# Sheet1.net
KiCad netlist of a schematic drawn in Altium Designer
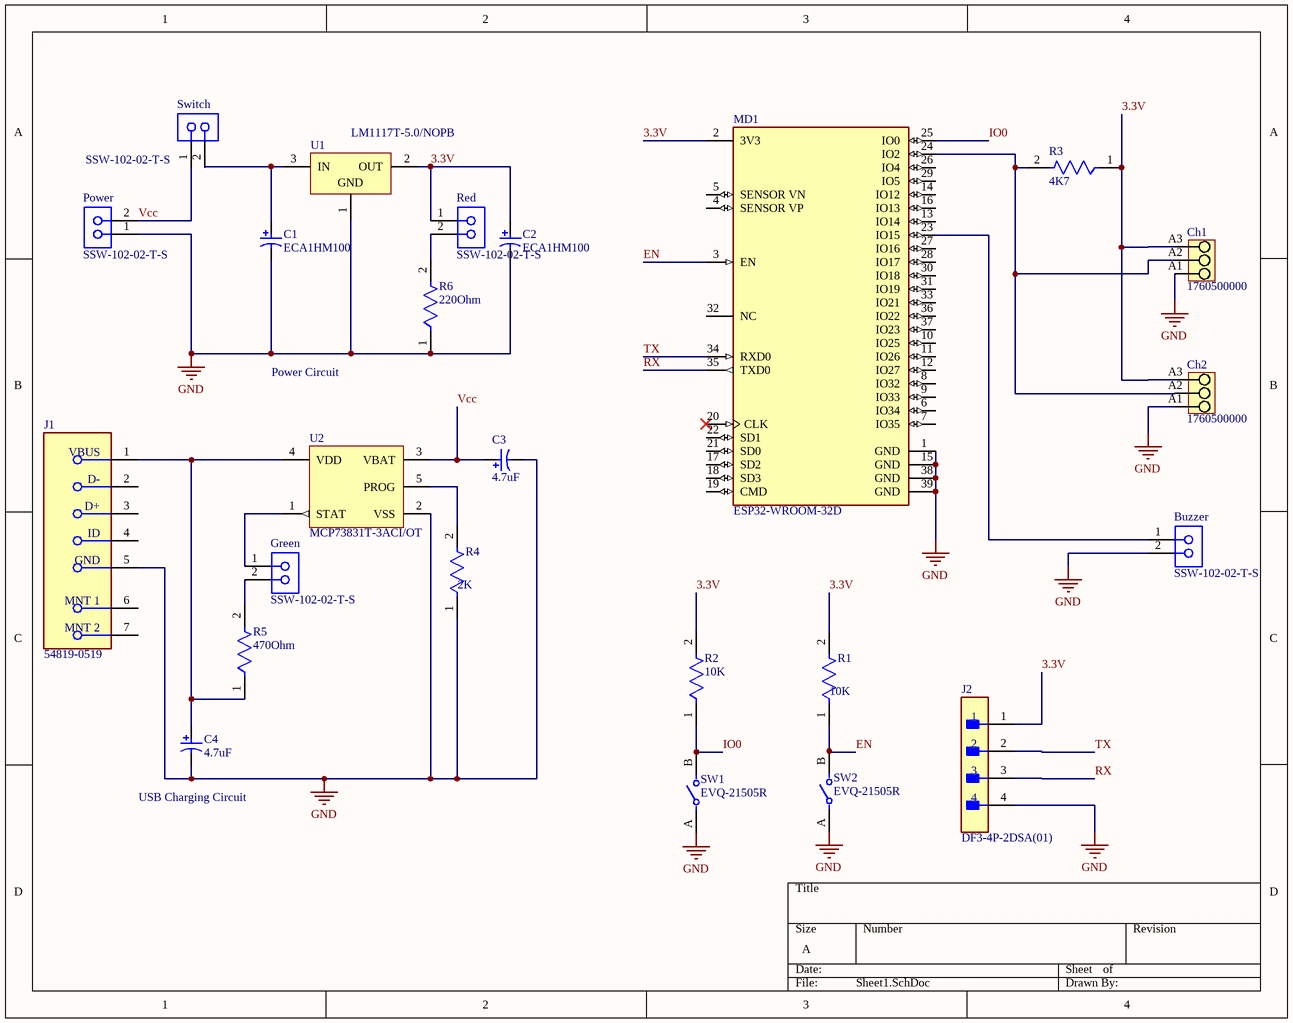
[diagram p0: Sheet1.SchDoc]

(export (version "E")
  (design (tool "Eeschema 10.0.6"))
  (components
    (comp (ref "Buzzer")
      (value "SSW-102-02-T-S")
      (footprint "SMTC-SSW-102-02-X-S")
      (description "SQ Post Socket, Through-hole, Vertical, -55 to 105 degC, 2.54 mm Pitch, 2-Pin, Female, RoHS")
      (fields (field (name "MANUFACTURER") "Samtec"))
      (libsource (lib "Altium Content Vault") (part "SMTC-SSW-102-02-X-S-X"))
    )
    (comp (ref "C1")
      (value "ECA1HM100")
      (footprint "CAPPR55-200-1100X500X1200")
      (description "Aluminum Electrolytic Capacitor, 10 uF, +/- 20%, 50 V, -40 to 85 degC, 2-Pin THD, RoHS, Bulk")
      (fields (field (name "MANUFACTURER") "Panasonic") (field (name "TOLERANCE") "20%"))
      (libsource (lib "Altium Content Vault") (part "CAP-P-2"))
    )
    (comp (ref "C2")
      (value "ECA1HM100")
      (footprint "CAPPR55-200-1100X500X1200")
      (description "Aluminum Electrolytic Capacitor, 10 uF, +/- 20%, 50 V, -40 to 85 degC, 2-Pin THD, RoHS, Bulk")
      (fields (field (name "MANUFACTURER") "Panasonic") (field (name "TOLERANCE") "20%"))
      (libsource (lib "Altium Content Vault") (part "CAP-P-2"))
    )
    (comp (ref "C3")
      (value "4.7uF")
      (footprint "CAPPR55-200-1100X500X1200")
      (description "Aluminum Electrolytic Capacitor, 4.7 uF, +/- 20%, 50 V, -40 to 85 degC, 2-Pin THD, RoHS, Bulk")
      (fields (field (name "VOLTAGE") "50V") (field (name "MANUFACTURER") "Panasonic"))
      (libsource (lib "Altium Content Vault") (part "CAP-P-2"))
    )
    (comp (ref "C4")
      (value "4.7uF")
      (footprint "CAPPR55-200-1100X500X1200")
      (description "Aluminum Electrolytic Capacitor, 4.7 uF, +/- 20%, 50 V, -40 to 85 degC, 2-Pin THD, RoHS, Bulk")
      (fields (field (name "VOLTAGE") "50V") (field (name "MANUFACTURER") "Panasonic"))
      (libsource (lib "Altium Content Vault") (part "CAP-P-2"))
    )
    (comp (ref "Ch1")
      (value "1760500000")
      (footprint "PM_5_08_90_03")
      (description "OMNIMATE Signal - series PM")
      (fields (field (name "MANUFACTURER") "Weidmueller"))
      (libsource (lib "Altium Content Vault") (part "Terminal_03_1x03"))
    )
    (comp (ref "Ch2")
      (value "1760500000")
      (footprint "PM_5_08_90_03")
      (description "OMNIMATE Signal - series PM")
      (fields (field (name "MANUFACTURER") "Weidmueller"))
      (libsource (lib "Altium Content Vault") (part "Terminal_03_1x03"))
    )
    (comp (ref "Green")
      (value "SSW-102-02-T-S")
      (footprint "SMTC-SSW-102-02-X-S")
      (description "SQ Post Socket, Through-hole, Vertical, -55 to 105 degC, 2.54 mm Pitch, 2-Pin, Female, RoHS")
      (fields (field (name "MANUFACTURER") "Samtec"))
      (libsource (lib "Altium Content Vault") (part "SMTC-SSW-102-02-X-S-X"))
    )
    (comp (ref "J1")
      (value "54819-0519")
      (footprint "FP-54819-0519-MFG")
      (description "CONN RCPT USB2.0 MINI B 5P R/A")
      (libsource (lib "Altium Content Vault") (part "0bee2869d159fa7a73e2a5ef735a9a6"))
    )
    (comp (ref "J2")
      (value "DF3-4P-2DSA(01)")
      (footprint "FP-DF3-4P-2DSA_01-MFG")
      (description "CONN HEADER VERT 4POS 2MM")
      (libsource (lib "Altium Content Vault") (part "299a8cea1bdcbc3624fe62c390fa72c"))
    )
    (comp (ref "MD1")
      (value "ESP32-WROOM-32D")
      (footprint "FP-ESP32-WROOM-32D-MFG")
      (description "WIFI MODULE 32MBITS SPI FLASH")
      (fields
        (field (name "OCTOPART") "https://octopart.com/esp32-wroom-32d-espressif+systems-91040050")
        (field (name "MANUFACTURER") "Espressif Systems")
      )
      (libsource (lib "Altium Content Vault") (part "a031a76f8c27026a7a7f4657ff233a3"))
    )
    (comp (ref "Power")
      (value "SSW-102-02-T-S")
      (footprint "SMTC-SSW-102-02-X-S")
      (description "SQ Post Socket, Through-hole, Vertical, -55 to 105 degC, 2.54 mm Pitch, 2-Pin, Female, RoHS")
      (fields (field (name "MANUFACTURER") "Samtec"))
      (libsource (lib "Altium Content Vault") (part "SMTC-SSW-102-02-X-S-X"))
    )
    (comp (ref "R1")
      (value "10K")
      (footprint "FP-CF18-MFG")
      (description "RES 10K OHM 1/8W 5% CF AXIAL")
      (fields
        (field (name "MANUFACTURER PART NUMBER") "CF18JT10K0")
        (field (name "MANUFACTURER") "Stackpole Electronics")
      )
      (libsource (lib "Altium Content Vault") (part "1029c3af85768c4190bb7ad29bc67b5"))
    )
    (comp (ref "R2")
      (value "10K")
      (footprint "FP-CF18-MFG")
      (description "RES 10K OHM 1/8W 5% CF AXIAL")
      (fields
        (field (name "MANUFACTURER PART NUMBER") "CF18JT10K0")
        (field (name "MANUFACTURER") "Stackpole Electronics")
      )
      (libsource (lib "Altium Content Vault") (part "1029c3af85768c4190bb7ad29bc67b5"))
    )
    (comp (ref "R3")
      (value "4K7")
      (footprint "FP-CF18-MFG")
      (description "RES 10K OHM 1/8W 5% CF AXIAL")
      (fields
        (field (name "MANUFACTURER PART NUMBER") "CF18JT10K0")
        (field (name "MANUFACTURER") "Stackpole Electronics")
      )
      (libsource (lib "Altium Content Vault") (part "1029c3af85768c4190bb7ad29bc67b5"))
    )
    (comp (ref "R4")
      (value "2K")
      (footprint "FP-CF18-MFG")
      (description "RES 10K OHM 1/8W 5% CF AXIAL")
      (fields
        (field (name "MANUFACTURER PART NUMBER") "CF18JT10K0")
        (field (name "MANUFACTURER") "Stackpole Electronics")
      )
      (libsource (lib "Altium Content Vault") (part "1029c3af85768c4190bb7ad29bc67b5"))
    )
    (comp (ref "R5")
      (value "470Ohm")
      (footprint "FP-CF18-MFG")
      (description "RES 10K OHM 1/8W 5% CF AXIAL")
      (fields
        (field (name "MANUFACTURER PART NUMBER") "CF18JT10K0")
        (field (name "MANUFACTURER") "Stackpole Electronics")
      )
      (libsource (lib "Altium Content Vault") (part "1029c3af85768c4190bb7ad29bc67b5"))
    )
    (comp (ref "R6")
      (value "220Ohm")
      (footprint "FP-CF18-MFG")
      (description "RES 10K OHM 1/8W 5% CF AXIAL")
      (fields
        (field (name "MANUFACTURER PART NUMBER") "CF18JT10K0")
        (field (name "MANUFACTURER") "Stackpole Electronics")
      )
      (libsource (lib "Altium Content Vault") (part "1029c3af85768c4190bb7ad29bc67b5"))
    )
    (comp (ref "Red")
      (value "SSW-102-02-T-S")
      (footprint "SMTC-SSW-102-02-X-S")
      (description "SQ Post Socket, Through-hole, Vertical, -55 to 105 degC, 2.54 mm Pitch, 2-Pin, Female, RoHS")
      (fields (field (name "MANUFACTURER") "Samtec"))
      (libsource (lib "Altium Content Vault") (part "SMTC-SSW-102-02-X-S-X"))
    )
    (comp (ref "SW1")
      (value "EVQ-21505R")
      (footprint "FP-EVQ-21505R-MFG")
      (description "SWITCH TACTILE SPST-NO 0.02A 15V")
      (libsource (lib "Altium Content Vault") (part "2b0b2b19372efd94fa7681498149756"))
    )
    (comp (ref "SW2")
      (value "EVQ-21505R")
      (footprint "FP-EVQ-21505R-MFG")
      (description "SWITCH TACTILE SPST-NO 0.02A 15V")
      (libsource (lib "Altium Content Vault") (part "2b0b2b19372efd94fa7681498149756"))
    )
    (comp (ref "Switch")
      (value "SSW-102-02-T-S")
      (footprint "SMTC-SSW-102-02-X-S")
      (description "SQ Post Socket, Through-hole, Vertical, -55 to 105 degC, 2.54 mm Pitch, 2-Pin, Female, RoHS")
      (fields (field (name "MANUFACTURER") "Samtec"))
      (libsource (lib "Altium Content Vault") (part "SMTC-SSW-102-02-X-S-X"))
    )
    (comp (ref "U1")
      (value "LM1117T-5.0/NOPB")
      (footprint "NDE0003A")
      (description "800mA Low-Dropout Linear Regulator, 3-pin TO-220, Pb-Free")
      (fields (field (name "MANUFACTURER") "Texas Instruments"))
      (libsource (lib "Altium Content Vault") (part "PM-REG-LM1086-SIL3"))
    )
    (comp (ref "U2")
      (value "MCP73831T-3ACI/OT")
      (footprint "SOT-23-OT5_M")
      (libsource (lib "Altium Content Vault") (part "PM-BM-MCP73831-SOT5"))
    )
  )
  (nets
    (net (code "1") (name "/3.3V") (class "Default")
      (node (ref "C2") (pin "1") (pinfunction "1_1") (pintype "passive"))
      (node (ref "Ch1") (pin "A3") (pinfunction "A3_A3") (pintype "passive"))
      (node (ref "Ch2") (pin "A3") (pinfunction "A3_A3") (pintype "passive"))
      (node (ref "J2") (pin "1") (pinfunction "1_1") (pintype "passive"))
      (node (ref "MD1") (pin "2") (pinfunction "3V3_2") (pintype "power_in"))
      (node (ref "R1") (pin "2") (pinfunction "2_2") (pintype "passive"))
      (node (ref "R2") (pin "2") (pinfunction "2_2") (pintype "passive"))
      (node (ref "R3") (pin "1") (pinfunction "1_1") (pintype "passive"))
      (node (ref "Red") (pin "1") (pinfunction "1_1") (pintype "passive"))
      (node (ref "U1") (pin "2") (pinfunction "OUT_2") (pintype "power_in"))
    )
    (net (code "2") (name "/EN") (class "Default")
      (node (ref "MD1") (pin "3") (pinfunction "EN_3") (pintype "input"))
      (node (ref "R1") (pin "1") (pinfunction "1_1") (pintype "passive"))
      (node (ref "SW2") (pin "B") (pinfunction "B_B") (pintype "passive"))
    )
    (net (code "3") (name "/IO0") (class "Default")
      (node (ref "MD1") (pin "25") (pinfunction "IO0_25") (pintype "bidirectional"))
      (node (ref "R2") (pin "1") (pinfunction "1_1") (pintype "passive"))
      (node (ref "SW1") (pin "B") (pinfunction "B_B") (pintype "passive"))
    )
    (net (code "4") (name "/RX") (class "Default")
      (node (ref "J2") (pin "3") (pinfunction "3_3") (pintype "passive"))
      (node (ref "MD1") (pin "35") (pinfunction "TXD0_35") (pintype "output"))
    )
    (net (code "5") (name "/TX") (class "Default")
      (node (ref "J2") (pin "2") (pinfunction "2_2") (pintype "passive"))
      (node (ref "MD1") (pin "34") (pinfunction "RXD0_34") (pintype "input"))
    )
    (net (code "6") (name "/Vcc") (class "Default")
      (node (ref "C3") (pin "1") (pinfunction "1_1") (pintype "passive"))
      (node (ref "Power") (pin "2") (pinfunction "2_2") (pintype "passive"))
      (node (ref "Switch") (pin "1") (pinfunction "1_1") (pintype "passive"))
      (node (ref "U2") (pin "3") (pinfunction "VBAT_3") (pintype "power_in"))
    )
    (net (code "7") (name "GND") (class "Default")
      (node (ref "Buzzer") (pin "2") (pinfunction "2_2") (pintype "passive"))
      (node (ref "C1") (pin "2") (pinfunction "2_2") (pintype "passive"))
      (node (ref "C2") (pin "2") (pinfunction "2_2") (pintype "passive"))
      (node (ref "C3") (pin "2") (pinfunction "2_2") (pintype "passive"))
      (node (ref "C4") (pin "2") (pinfunction "2_2") (pintype "passive"))
      (node (ref "Ch1") (pin "A1") (pinfunction "A1_A1") (pintype "passive"))
      (node (ref "Ch2") (pin "A1") (pinfunction "A1_A1") (pintype "passive"))
      (node (ref "J1") (pin "5") (pinfunction "GND_5") (pintype "power_in"))
      (node (ref "J2") (pin "4") (pinfunction "4_4") (pintype "passive"))
      (node (ref "MD1") (pin "1") (pinfunction "GND_1") (pintype "power_in"))
      (node (ref "MD1") (pin "15") (pinfunction "GND_15") (pintype "power_in"))
      (node (ref "MD1") (pin "38") (pinfunction "GND_38") (pintype "power_in"))
      (node (ref "MD1") (pin "39") (pinfunction "GND_39") (pintype "power_in"))
      (node (ref "Power") (pin "1") (pinfunction "1_1") (pintype "passive"))
      (node (ref "R4") (pin "1") (pinfunction "1_1") (pintype "passive"))
      (node (ref "R6") (pin "1") (pinfunction "1_1") (pintype "passive"))
      (node (ref "SW1") (pin "A") (pinfunction "A_A") (pintype "passive"))
      (node (ref "SW2") (pin "A") (pinfunction "A_A") (pintype "passive"))
      (node (ref "U1") (pin "1") (pinfunction "GND_1") (pintype "power_in"))
      (node (ref "U2") (pin "2") (pinfunction "VSS_2") (pintype "power_in"))
    )
    (net (code "8") (name "Net-(Green-Pad2)") (class "Default")
      (node (ref "Green") (pin "2") (pinfunction "2_2") (pintype "passive"))
      (node (ref "R5") (pin "2") (pinfunction "2_2") (pintype "passive"))
    )
    (net (code "9") (name "Net-(J1-VBUS)") (class "Default")
      (node (ref "C4") (pin "1") (pinfunction "1_1") (pintype "passive"))
      (node (ref "J1") (pin "1") (pinfunction "VBUS_1") (pintype "power_in"))
      (node (ref "R5") (pin "1") (pinfunction "1_1") (pintype "passive"))
      (node (ref "U2") (pin "4") (pinfunction "VDD_4") (pintype "power_in"))
    )
    (net (code "10") (name "Net-(MD1-IO2)") (class "Default")
      (node (ref "Ch1") (pin "A2") (pinfunction "A2_A2") (pintype "passive"))
      (node (ref "Ch2") (pin "A2") (pinfunction "A2_A2") (pintype "passive"))
      (node (ref "MD1") (pin "24") (pinfunction "IO2_24") (pintype "bidirectional"))
      (node (ref "R3") (pin "2") (pinfunction "2_2") (pintype "passive"))
    )
    (net (code "11") (name "Net-(MD1-IO15)") (class "Default")
      (node (ref "Buzzer") (pin "1") (pinfunction "1_1") (pintype "passive"))
      (node (ref "MD1") (pin "23") (pinfunction "IO15_23") (pintype "bidirectional"))
    )
    (net (code "12") (name "Net-(R6-Pad2)") (class "Default")
      (node (ref "R6") (pin "2") (pinfunction "2_2") (pintype "passive"))
      (node (ref "Red") (pin "2") (pinfunction "2_2") (pintype "passive"))
    )
    (net (code "13") (name "Net-(U1-IN)") (class "Default")
      (node (ref "C1") (pin "1") (pinfunction "1_1") (pintype "passive"))
      (node (ref "Switch") (pin "2") (pinfunction "2_2") (pintype "passive"))
      (node (ref "U1") (pin "3") (pinfunction "IN_3") (pintype "power_in"))
    )
    (net (code "14") (name "Net-(U2-PROG)") (class "Default")
      (node (ref "R4") (pin "2") (pinfunction "2_2") (pintype "passive"))
      (node (ref "U2") (pin "5") (pinfunction "PROG_5") (pintype "passive"))
    )
    (net (code "15") (name "Net-(U2-STAT)") (class "Default")
      (node (ref "Green") (pin "1") (pinfunction "1_1") (pintype "passive"))
      (node (ref "U2") (pin "1") (pinfunction "STAT_1") (pintype "output"))
    )
    (net (code "16") (name "unconnected-(J1-D+-Pad3)") (class "Default")
      (node (ref "J1") (pin "3") (pinfunction "D+_3") (pintype "passive"))
    )
    (net (code "17") (name "unconnected-(J1-D--Pad2)") (class "Default")
      (node (ref "J1") (pin "2") (pinfunction "D-_2") (pintype "passive"))
    )
    (net (code "18") (name "unconnected-(J1-ID-Pad4)") (class "Default")
      (node (ref "J1") (pin "4") (pinfunction "ID_4") (pintype "passive"))
    )
    (net (code "19") (name "unconnected-(J1-MNT_1-Pad6)") (class "Default")
      (node (ref "J1") (pin "6") (pinfunction "MNT_1_6") (pintype "passive"))
    )
    (net (code "20") (name "unconnected-(J1-MNT_2-Pad7)") (class "Default")
      (node (ref "J1") (pin "7") (pinfunction "MNT_2_7") (pintype "passive"))
    )
    (net (code "21") (name "unconnected-(MD1-CLK-Pad20)") (class "Default")
      (node (ref "MD1") (pin "20") (pinfunction "CLK_20") (pintype "input+no_connect"))
    )
    (net (code "22") (name "unconnected-(MD1-CMD-Pad19)") (class "Default")
      (node (ref "MD1") (pin "19") (pinfunction "CMD_19") (pintype "bidirectional"))
    )
    (net (code "23") (name "unconnected-(MD1-IO4-Pad26)") (class "Default")
      (node (ref "MD1") (pin "26") (pinfunction "IO4_26") (pintype "bidirectional"))
    )
    (net (code "24") (name "unconnected-(MD1-IO5-Pad29)") (class "Default")
      (node (ref "MD1") (pin "29") (pinfunction "IO5_29") (pintype "bidirectional"))
    )
    (net (code "25") (name "unconnected-(MD1-IO12-Pad14)") (class "Default")
      (node (ref "MD1") (pin "14") (pinfunction "IO12_14") (pintype "bidirectional"))
    )
    (net (code "26") (name "unconnected-(MD1-IO13-Pad16)") (class "Default")
      (node (ref "MD1") (pin "16") (pinfunction "IO13_16") (pintype "bidirectional"))
    )
    (net (code "27") (name "unconnected-(MD1-IO14-Pad13)") (class "Default")
      (node (ref "MD1") (pin "13") (pinfunction "IO14_13") (pintype "bidirectional"))
    )
    (net (code "28") (name "unconnected-(MD1-IO16-Pad27)") (class "Default")
      (node (ref "MD1") (pin "27") (pinfunction "IO16_27") (pintype "bidirectional"))
    )
    (net (code "29") (name "unconnected-(MD1-IO17-Pad28)") (class "Default")
      (node (ref "MD1") (pin "28") (pinfunction "IO17_28") (pintype "bidirectional"))
    )
    (net (code "30") (name "unconnected-(MD1-IO18-Pad30)") (class "Default")
      (node (ref "MD1") (pin "30") (pinfunction "IO18_30") (pintype "bidirectional"))
    )
    (net (code "31") (name "unconnected-(MD1-IO19-Pad31)") (class "Default")
      (node (ref "MD1") (pin "31") (pinfunction "IO19_31") (pintype "bidirectional"))
    )
    (net (code "32") (name "unconnected-(MD1-IO21-Pad33)") (class "Default")
      (node (ref "MD1") (pin "33") (pinfunction "IO21_33") (pintype "bidirectional"))
    )
    (net (code "33") (name "unconnected-(MD1-IO22-Pad36)") (class "Default")
      (node (ref "MD1") (pin "36") (pinfunction "IO22_36") (pintype "bidirectional"))
    )
    (net (code "34") (name "unconnected-(MD1-IO23-Pad37)") (class "Default")
      (node (ref "MD1") (pin "37") (pinfunction "IO23_37") (pintype "bidirectional"))
    )
    (net (code "35") (name "unconnected-(MD1-IO25-Pad10)") (class "Default")
      (node (ref "MD1") (pin "10") (pinfunction "IO25_10") (pintype "bidirectional"))
    )
    (net (code "36") (name "unconnected-(MD1-IO26-Pad11)") (class "Default")
      (node (ref "MD1") (pin "11") (pinfunction "IO26_11") (pintype "bidirectional"))
    )
    (net (code "37") (name "unconnected-(MD1-IO27-Pad12)") (class "Default")
      (node (ref "MD1") (pin "12") (pinfunction "IO27_12") (pintype "bidirectional"))
    )
    (net (code "38") (name "unconnected-(MD1-IO32-Pad8)") (class "Default")
      (node (ref "MD1") (pin "8") (pinfunction "IO32_8") (pintype "bidirectional"))
    )
    (net (code "39") (name "unconnected-(MD1-IO33-Pad9)") (class "Default")
      (node (ref "MD1") (pin "9") (pinfunction "IO33_9") (pintype "bidirectional"))
    )
    (net (code "40") (name "unconnected-(MD1-IO34-Pad6)") (class "Default")
      (node (ref "MD1") (pin "6") (pinfunction "IO34_6") (pintype "bidirectional"))
    )
    (net (code "41") (name "unconnected-(MD1-IO35-Pad7)") (class "Default")
      (node (ref "MD1") (pin "7") (pinfunction "IO35_7") (pintype "bidirectional"))
    )
    (net (code "42") (name "unconnected-(MD1-NC-Pad32)") (class "Default")
      (node (ref "MD1") (pin "32") (pinfunction "NC_32") (pintype "passive"))
    )
    (net (code "43") (name "unconnected-(MD1-SD0-Pad21)") (class "Default")
      (node (ref "MD1") (pin "21") (pinfunction "SD0_21") (pintype "bidirectional"))
    )
    (net (code "44") (name "unconnected-(MD1-SD1-Pad22)") (class "Default")
      (node (ref "MD1") (pin "22") (pinfunction "SD1_22") (pintype "bidirectional"))
    )
    (net (code "45") (name "unconnected-(MD1-SD2-Pad17)") (class "Default")
      (node (ref "MD1") (pin "17") (pinfunction "SD2_17") (pintype "bidirectional"))
    )
    (net (code "46") (name "unconnected-(MD1-SD3-Pad18)") (class "Default")
      (node (ref "MD1") (pin "18") (pinfunction "SD3_18") (pintype "bidirectional"))
    )
    (net (code "47") (name "unconnected-(MD1-SENSOR_VN-Pad5)") (class "Default")
      (node (ref "MD1") (pin "5") (pinfunction "SENSOR_VN_5") (pintype "bidirectional"))
    )
    (net (code "48") (name "unconnected-(MD1-SENSOR_VP-Pad4)") (class "Default")
      (node (ref "MD1") (pin "4") (pinfunction "SENSOR_VP_4") (pintype "bidirectional"))
    )
  )
)
